# echo.net
KiCad netlist of a schematic drawn in Altium Designer
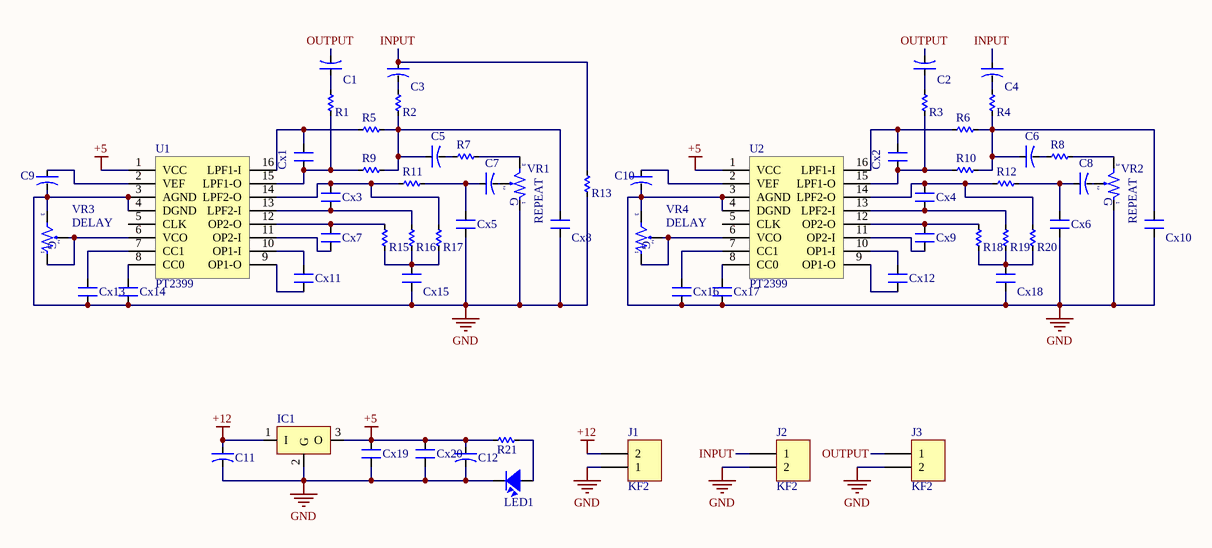
[diagram p0: echo.SchDoc]

(export (version "E")
  (design (tool "Eeschema 10.0.6"))
  (components
    (comp (ref "C1")
      (value "CN-ALU-DIP")
      (footprint "CA-ALU-5")
      (description "Capacitor (Semiconductor SIM Model)")
      (fields (field (name "PUBLISHER") "Altium Limited"))
      (libsource (lib "LIBRARY") (part "CN-ALU-DIP"))
    )
    (comp (ref "C2")
      (value "CN-ALU-DIP")
      (footprint "CA-ALU-5")
      (description "Capacitor (Semiconductor SIM Model)")
      (fields (field (name "PUBLISHER") "Altium Limited"))
      (libsource (lib "LIBRARY") (part "CN-ALU-DIP"))
    )
    (comp (ref "C3")
      (value "CN-ALU-DIP")
      (footprint "CA-ALU-5")
      (description "Capacitor (Semiconductor SIM Model)")
      (fields (field (name "PUBLISHER") "Altium Limited"))
      (libsource (lib "LIBRARY") (part "CN-ALU-DIP"))
    )
    (comp (ref "C4")
      (value "CN-ALU-DIP")
      (footprint "CA-ALU-5")
      (description "Capacitor (Semiconductor SIM Model)")
      (fields (field (name "PUBLISHER") "Altium Limited"))
      (libsource (lib "LIBRARY") (part "CN-ALU-DIP"))
    )
    (comp (ref "C5")
      (value "CN-ALU-DIP")
      (footprint "CA-ALU-5")
      (description "Capacitor (Semiconductor SIM Model)")
      (fields (field (name "PUBLISHER") "Altium Limited"))
      (libsource (lib "LIBRARY") (part "CN-ALU-DIP"))
    )
    (comp (ref "C6")
      (value "CN-ALU-DIP")
      (footprint "CA-ALU-5")
      (description "Capacitor (Semiconductor SIM Model)")
      (fields (field (name "PUBLISHER") "Altium Limited"))
      (libsource (lib "LIBRARY") (part "CN-ALU-DIP"))
    )
    (comp (ref "C7")
      (value "CN-ALU-DIP")
      (footprint "CA-ALU-5")
      (description "Capacitor (Semiconductor SIM Model)")
      (fields (field (name "PUBLISHER") "Altium Limited"))
      (libsource (lib "LIBRARY") (part "CN-ALU-DIP"))
    )
    (comp (ref "C8")
      (value "CN-ALU-DIP")
      (footprint "CA-ALU-5")
      (description "Capacitor (Semiconductor SIM Model)")
      (fields (field (name "PUBLISHER") "Altium Limited"))
      (libsource (lib "LIBRARY") (part "CN-ALU-DIP"))
    )
    (comp (ref "C9")
      (value "CN-ALU-DIP")
      (footprint "CA-ALU-5")
      (description "Capacitor (Semiconductor SIM Model)")
      (fields (field (name "PUBLISHER") "Altium Limited"))
      (libsource (lib "LIBRARY") (part "CN-ALU-DIP"))
    )
    (comp (ref "C10")
      (value "CN-ALU-DIP")
      (footprint "CA-ALU-5")
      (description "Capacitor (Semiconductor SIM Model)")
      (fields (field (name "PUBLISHER") "Altium Limited"))
      (libsource (lib "LIBRARY") (part "CN-ALU-DIP"))
    )
    (comp (ref "C11")
      (value "CN-ALU-DIP")
      (footprint "CA-ALU-6.3")
      (description "Capacitor (Semiconductor SIM Model)")
      (fields (field (name "PUBLISHER") "Altium Limited"))
      (libsource (lib "LIBRARY") (part "CN-ALU-DIP"))
    )
    (comp (ref "C12")
      (value "CN-ALU-DIP")
      (footprint "CA-ALU-8")
      (description "Capacitor (Semiconductor SIM Model)")
      (fields (field (name "PUBLISHER") "Altium Limited"))
      (libsource (lib "LIBRARY") (part "CN-ALU-DIP"))
    )
    (comp (ref "Cx1") (value "XXpF") (footprint "CN1.5") (libsource (lib "LIBRARY") (part "CN")))
    (comp (ref "Cx2") (value "XXpF") (footprint "CN1.5") (libsource (lib "LIBRARY") (part "CN")))
    (comp (ref "Cx3") (value "XXpF") (footprint "CN1.5") (libsource (lib "LIBRARY") (part "CN")))
    (comp (ref "Cx4") (value "XXpF") (footprint "CN1.5") (libsource (lib "LIBRARY") (part "CN")))
    (comp (ref "Cx5") (value "XXpF") (footprint "CN1.5") (libsource (lib "LIBRARY") (part "CN")))
    (comp (ref "Cx6") (value "XXpF") (footprint "CN1.5") (libsource (lib "LIBRARY") (part "CN")))
    (comp (ref "Cx7") (value "XXpF") (footprint "CN1.5") (libsource (lib "LIBRARY") (part "CN")))
    (comp (ref "Cx8") (value "XXpF") (footprint "CN1.5") (libsource (lib "LIBRARY") (part "CN")))
    (comp (ref "Cx9") (value "XXpF") (footprint "CN1.5") (libsource (lib "LIBRARY") (part "CN")))
    (comp (ref "Cx10") (value "XXpF") (footprint "CN1.5") (libsource (lib "LIBRARY") (part "CN")))
    (comp (ref "Cx11") (value "XXpF") (footprint "CN1.5") (libsource (lib "LIBRARY") (part "CN")))
    (comp (ref "Cx12") (value "XXpF") (footprint "CN1.5") (libsource (lib "LIBRARY") (part "CN")))
    (comp (ref "Cx13") (value "XXpF") (footprint "CN1.5") (libsource (lib "LIBRARY") (part "CN")))
    (comp (ref "Cx14") (value "XXpF") (footprint "CN1.5") (libsource (lib "LIBRARY") (part "CN")))
    (comp (ref "Cx15") (value "XXpF") (footprint "CN1.5") (libsource (lib "LIBRARY") (part "CN")))
    (comp (ref "Cx16") (value "XXpF") (footprint "CN1.5") (libsource (lib "LIBRARY") (part "CN")))
    (comp (ref "Cx17") (value "XXpF") (footprint "CN1.5") (libsource (lib "LIBRARY") (part "CN")))
    (comp (ref "Cx18") (value "XXpF") (footprint "CN1.5") (libsource (lib "LIBRARY") (part "CN")))
    (comp (ref "Cx19") (value "XXpF") (footprint "CN1.5") (libsource (lib "LIBRARY") (part "CN")))
    (comp (ref "Cx20") (value "XXpF") (footprint "CN1.5") (libsource (lib "LIBRARY") (part "CN")))
    (comp (ref "IC1")
      (value "LM78xx")
      (footprint "TO220-123")
      (description "Positive Voltage Regulator")
      (fields (field (name "PUBLISHER") "Altium Limited"))
      (libsource (lib "LIBRARY") (part "LM78xx"))
    )
    (comp (ref "J1")
      (value "KF2")
      (footprint "KF2-5.08")
      (fields
        (field (name "MANUFACTURER") "Würth Elektronik eiSos GmbH")
        (field (name "PARTNO") "691103110002")
        (field (name "CREATED BY") "Karrer Zheng")
      )
      (libsource (lib "") (part "KF2_1"))
    )
    (comp (ref "J2")
      (value "KF2")
      (footprint "KF2-5.08")
      (fields
        (field (name "MANUFACTURER") "Würth Elektronik eiSos GmbH")
        (field (name "PARTNO") "691103110002")
        (field (name "CREATED BY") "Karrer Zheng")
      )
      (libsource (lib "LIBRARY") (part "KF2"))
    )
    (comp (ref "J3")
      (value "KF2")
      (footprint "KF2-5.08")
      (fields
        (field (name "MANUFACTURER") "Würth Elektronik eiSos GmbH")
        (field (name "PARTNO") "691103110002")
        (field (name "CREATED BY") "Karrer Zheng")
      )
      (libsource (lib "LIBRARY") (part "KF2"))
    )
    (comp (ref "LED1")
      (value "LED")
      (footprint "LED-5-BLUE")
      (description "LED Single colour Green and Red")
      (libsource (lib "LIBRARY") (part "LED"))
    )
    (comp (ref "R1")
      (value "Res")
      (footprint "RES-1/4W-SMALL")
      (fields
        (field (name "MANUFACTURER") "Generic Components")
        (field (name "PUBLISHER") "Altium Hobart Technology Centre")
      )
      (libsource (lib "LIBRARY") (part "Res"))
    )
    (comp (ref "R2")
      (value "Res")
      (footprint "RES-1/4W-SMALL")
      (fields
        (field (name "MANUFACTURER") "Generic Components")
        (field (name "PUBLISHER") "Altium Hobart Technology Centre")
      )
      (libsource (lib "LIBRARY") (part "Res"))
    )
    (comp (ref "R3")
      (value "Res")
      (footprint "RES-1/4W-SMALL")
      (fields
        (field (name "MANUFACTURER") "Generic Components")
        (field (name "PUBLISHER") "Altium Hobart Technology Centre")
      )
      (libsource (lib "LIBRARY") (part "Res"))
    )
    (comp (ref "R4")
      (value "Res")
      (footprint "RES-1/4W-SMALL")
      (fields
        (field (name "MANUFACTURER") "Generic Components")
        (field (name "PUBLISHER") "Altium Hobart Technology Centre")
      )
      (libsource (lib "LIBRARY") (part "Res"))
    )
    (comp (ref "R5")
      (value "Res")
      (footprint "RES-1/4W-SMALL")
      (fields
        (field (name "MANUFACTURER") "Generic Components")
        (field (name "PUBLISHER") "Altium Hobart Technology Centre")
      )
      (libsource (lib "LIBRARY") (part "Res"))
    )
    (comp (ref "R6")
      (value "Res")
      (footprint "RES-1/4W-SMALL")
      (fields
        (field (name "MANUFACTURER") "Generic Components")
        (field (name "PUBLISHER") "Altium Hobart Technology Centre")
      )
      (libsource (lib "LIBRARY") (part "Res"))
    )
    (comp (ref "R7")
      (value "Res")
      (footprint "RES-1/4W-SMALL")
      (fields
        (field (name "MANUFACTURER") "Generic Components")
        (field (name "PUBLISHER") "Altium Hobart Technology Centre")
      )
      (libsource (lib "LIBRARY") (part "Res"))
    )
    (comp (ref "R8")
      (value "Res")
      (footprint "RES-1/4W-SMALL")
      (fields
        (field (name "MANUFACTURER") "Generic Components")
        (field (name "PUBLISHER") "Altium Hobart Technology Centre")
      )
      (libsource (lib "LIBRARY") (part "Res"))
    )
    (comp (ref "R9")
      (value "Res")
      (footprint "RES-1/4W-SMALL")
      (fields
        (field (name "MANUFACTURER") "Generic Components")
        (field (name "PUBLISHER") "Altium Hobart Technology Centre")
      )
      (libsource (lib "LIBRARY") (part "Res"))
    )
    (comp (ref "R10")
      (value "Res")
      (footprint "RES-1/4W-SMALL")
      (fields
        (field (name "MANUFACTURER") "Generic Components")
        (field (name "PUBLISHER") "Altium Hobart Technology Centre")
      )
      (libsource (lib "LIBRARY") (part "Res"))
    )
    (comp (ref "R11")
      (value "Res")
      (footprint "RES-1/4W-SMALL")
      (fields
        (field (name "MANUFACTURER") "Generic Components")
        (field (name "PUBLISHER") "Altium Hobart Technology Centre")
      )
      (libsource (lib "LIBRARY") (part "Res"))
    )
    (comp (ref "R12")
      (value "Res")
      (footprint "RES-1/4W-SMALL")
      (fields
        (field (name "MANUFACTURER") "Generic Components")
        (field (name "PUBLISHER") "Altium Hobart Technology Centre")
      )
      (libsource (lib "LIBRARY") (part "Res"))
    )
    (comp (ref "R13")
      (value "Res")
      (footprint "RES-1/4W-SMALL")
      (fields
        (field (name "MANUFACTURER") "Generic Components")
        (field (name "PUBLISHER") "Altium Hobart Technology Centre")
      )
      (libsource (lib "LIBRARY") (part "Res"))
    )
    (comp (ref "R15")
      (value "Res")
      (footprint "RES-1/4W-SMALL")
      (fields
        (field (name "MANUFACTURER") "Generic Components")
        (field (name "PUBLISHER") "Altium Hobart Technology Centre")
      )
      (libsource (lib "LIBRARY") (part "Res"))
    )
    (comp (ref "R16")
      (value "Res")
      (footprint "RES-1/4W-SMALL")
      (fields
        (field (name "MANUFACTURER") "Generic Components")
        (field (name "PUBLISHER") "Altium Hobart Technology Centre")
      )
      (libsource (lib "LIBRARY") (part "Res"))
    )
    (comp (ref "R17")
      (value "Res")
      (footprint "RES-1/4W-SMALL")
      (fields
        (field (name "MANUFACTURER") "Generic Components")
        (field (name "PUBLISHER") "Altium Hobart Technology Centre")
      )
      (libsource (lib "LIBRARY") (part "Res"))
    )
    (comp (ref "R18")
      (value "Res")
      (footprint "RES-1/4W-SMALL")
      (fields
        (field (name "MANUFACTURER") "Generic Components")
        (field (name "PUBLISHER") "Altium Hobart Technology Centre")
      )
      (libsource (lib "LIBRARY") (part "Res"))
    )
    (comp (ref "R19")
      (value "Res")
      (footprint "RES-1/4W-SMALL")
      (fields
        (field (name "MANUFACTURER") "Generic Components")
        (field (name "PUBLISHER") "Altium Hobart Technology Centre")
      )
      (libsource (lib "LIBRARY") (part "Res"))
    )
    (comp (ref "R20")
      (value "Res")
      (footprint "RES-1/4W-SMALL")
      (fields
        (field (name "MANUFACTURER") "Generic Components")
        (field (name "PUBLISHER") "Altium Hobart Technology Centre")
      )
      (libsource (lib "LIBRARY") (part "Res"))
    )
    (comp (ref "R21")
      (value "Res")
      (footprint "RES-1/4W-SMALL")
      (fields
        (field (name "MANUFACTURER") "Generic Components")
        (field (name "PUBLISHER") "Altium Hobart Technology Centre")
      )
      (libsource (lib "LIBRARY") (part "Res"))
    )
    (comp (ref "U1")
      (value "PT2399")
      (footprint "DIP16")
      (description "Reverb")
      (libsource (lib "LIBRARY") (part "PT2399"))
    )
    (comp (ref "U2")
      (value "PT2399")
      (footprint "DIP16")
      (description "Reverb")
      (libsource (lib "LIBRARY") (part "PT2399"))
    )
    (comp (ref "VR1")
      (value "REPEAT")
      (footprint "VR-S1")
      (description "Var Resistor")
      (libsource (lib "LIBRARY") (part "VR-S"))
    )
    (comp (ref "VR2")
      (value "REPEAT")
      (footprint "VR-S1")
      (description "Var Resistor")
      (libsource (lib "LIBRARY") (part "VR-S"))
    )
    (comp (ref "VR3")
      (value "DELAY")
      (footprint "VR-S1")
      (description "Var Resistor")
      (libsource (lib "LIBRARY") (part "VR-S"))
    )
    (comp (ref "VR4")
      (value "DELAY")
      (footprint "VR-S1")
      (description "Var Resistor")
      (libsource (lib "LIBRARY") (part "VR-S"))
    )
  )
  (nets
    (net (code "1") (name "+5") (class "Default")
      (node (ref "C12") (pin "1") (pinfunction "1_1") (pintype "passive"))
      (node (ref "Cx19") (pin "2") (pinfunction "2_2") (pintype "passive"))
      (node (ref "Cx20") (pin "2") (pinfunction "2_2") (pintype "passive"))
      (node (ref "IC1") (pin "3") (pinfunction "O_3") (pintype "power_in"))
      (node (ref "R21") (pin "1") (pinfunction "1_1") (pintype "passive"))
      (node (ref "U1") (pin "1") (pinfunction "VCC_1") (pintype "passive"))
      (node (ref "U2") (pin "1") (pinfunction "VCC_1") (pintype "passive"))
    )
    (net (code "2") (name "+12") (class "Default")
      (node (ref "C11") (pin "1") (pinfunction "1_1") (pintype "passive"))
      (node (ref "IC1") (pin "1") (pinfunction "I_1") (pintype "power_in"))
      (node (ref "J1") (pin "2") (pinfunction "2_2") (pintype "passive"))
    )
    (net (code "3") (name "/INPUT") (class "Default")
      (node (ref "C3") (pin "1") (pinfunction "1_1") (pintype "passive"))
      (node (ref "C4") (pin "1") (pinfunction "1_1") (pintype "passive"))
      (node (ref "J2") (pin "1") (pinfunction "1_1") (pintype "passive"))
      (node (ref "R13") (pin "2") (pinfunction "2_2") (pintype "passive"))
    )
    (net (code "4") (name "/OUTPUT") (class "Default")
      (node (ref "C1") (pin "2") (pinfunction "2_2") (pintype "passive"))
      (node (ref "C2") (pin "2") (pinfunction "2_2") (pintype "passive"))
      (node (ref "J3") (pin "1") (pinfunction "1_1") (pintype "passive"))
    )
    (net (code "5") (name "GND") (class "Default")
      (node (ref "C10") (pin "2") (pinfunction "2_2") (pintype "passive"))
      (node (ref "C11") (pin "2") (pinfunction "2_2") (pintype "passive"))
      (node (ref "C12") (pin "2") (pinfunction "2_2") (pintype "passive"))
      (node (ref "C9") (pin "2") (pinfunction "2_2") (pintype "passive"))
      (node (ref "Cx10") (pin "2") (pinfunction "2_2") (pintype "passive"))
      (node (ref "Cx13") (pin "2") (pinfunction "2_2") (pintype "passive"))
      (node (ref "Cx14") (pin "2") (pinfunction "2_2") (pintype "passive"))
      (node (ref "Cx15") (pin "2") (pinfunction "2_2") (pintype "passive"))
      (node (ref "Cx16") (pin "2") (pinfunction "2_2") (pintype "passive"))
      (node (ref "Cx17") (pin "2") (pinfunction "2_2") (pintype "passive"))
      (node (ref "Cx18") (pin "2") (pinfunction "2_2") (pintype "passive"))
      (node (ref "Cx19") (pin "1") (pinfunction "1_1") (pintype "passive"))
      (node (ref "Cx20") (pin "1") (pinfunction "1_1") (pintype "passive"))
      (node (ref "Cx5") (pin "2") (pinfunction "2_2") (pintype "passive"))
      (node (ref "Cx6") (pin "2") (pinfunction "2_2") (pintype "passive"))
      (node (ref "Cx8") (pin "2") (pinfunction "2_2") (pintype "passive"))
      (node (ref "IC1") (pin "2") (pinfunction "G_2") (pintype "power_in"))
      (node (ref "J1") (pin "1") (pinfunction "1_1") (pintype "passive"))
      (node (ref "J2") (pin "2") (pinfunction "2_2") (pintype "passive"))
      (node (ref "J3") (pin "2") (pinfunction "2_2") (pintype "passive"))
      (node (ref "LED1") (pin "2") (pinfunction "2_2") (pintype "passive"))
      (node (ref "R13") (pin "1") (pinfunction "1_1") (pintype "passive"))
      (node (ref "U1") (pin "3") (pinfunction "AGND_3") (pintype "passive"))
      (node (ref "U1") (pin "4") (pinfunction "DGND_4") (pintype "passive"))
      (node (ref "U2") (pin "3") (pinfunction "AGND_3") (pintype "passive"))
      (node (ref "U2") (pin "4") (pinfunction "DGND_4") (pintype "passive"))
      (node (ref "VR1") (pin "1") (pinfunction "1_1") (pintype "passive"))
      (node (ref "VR2") (pin "1") (pinfunction "1_1") (pintype "passive"))
      (node (ref "VR3") (pin "3") (pinfunction "3_3") (pintype "passive"))
      (node (ref "VR4") (pin "3") (pinfunction "3_3") (pintype "passive"))
    )
    (net (code "6") (name "Net-(C1-Pad1)") (class "Default")
      (node (ref "C1") (pin "1") (pinfunction "1_1") (pintype "passive"))
      (node (ref "R1") (pin "1") (pinfunction "1_1") (pintype "passive"))
    )
    (net (code "7") (name "Net-(C2-Pad1)") (class "Default")
      (node (ref "C2") (pin "1") (pinfunction "1_1") (pintype "passive"))
      (node (ref "R3") (pin "1") (pinfunction "1_1") (pintype "passive"))
    )
    (net (code "8") (name "Net-(C3-Pad2)") (class "Default")
      (node (ref "C3") (pin "2") (pinfunction "2_2") (pintype "passive"))
      (node (ref "R2") (pin "2") (pinfunction "2_2") (pintype "passive"))
    )
    (net (code "9") (name "Net-(C4-Pad2)") (class "Default")
      (node (ref "C4") (pin "2") (pinfunction "2_2") (pintype "passive"))
      (node (ref "R4") (pin "2") (pinfunction "2_2") (pintype "passive"))
    )
    (net (code "10") (name "Net-(C5-Pad1)") (class "Default")
      (node (ref "C5") (pin "1") (pinfunction "1_1") (pintype "passive"))
      (node (ref "Cx8") (pin "1") (pinfunction "1_1") (pintype "passive"))
      (node (ref "R2") (pin "1") (pinfunction "1_1") (pintype "passive"))
      (node (ref "R5") (pin "1") (pinfunction "1_1") (pintype "passive"))
      (node (ref "R9") (pin "1") (pinfunction "1_1") (pintype "passive"))
    )
    (net (code "11") (name "Net-(C5-Pad2)") (class "Default")
      (node (ref "C5") (pin "2") (pinfunction "2_2") (pintype "passive"))
      (node (ref "R7") (pin "2") (pinfunction "2_2") (pintype "passive"))
    )
    (net (code "12") (name "Net-(C6-Pad1)") (class "Default")
      (node (ref "C6") (pin "1") (pinfunction "1_1") (pintype "passive"))
      (node (ref "Cx10") (pin "1") (pinfunction "1_1") (pintype "passive"))
      (node (ref "R10") (pin "1") (pinfunction "1_1") (pintype "passive"))
      (node (ref "R4") (pin "1") (pinfunction "1_1") (pintype "passive"))
      (node (ref "R6") (pin "1") (pinfunction "1_1") (pintype "passive"))
    )
    (net (code "13") (name "Net-(C6-Pad2)") (class "Default")
      (node (ref "C6") (pin "2") (pinfunction "2_2") (pintype "passive"))
      (node (ref "R8") (pin "2") (pinfunction "2_2") (pintype "passive"))
    )
    (net (code "14") (name "Net-(C7-Pad1)") (class "Default")
      (node (ref "C7") (pin "1") (pinfunction "1_1") (pintype "passive"))
      (node (ref "Cx5") (pin "1") (pinfunction "1_1") (pintype "passive"))
      (node (ref "R11") (pin "1") (pinfunction "1_1") (pintype "passive"))
    )
    (net (code "15") (name "Net-(C7-Pad2)") (class "Default")
      (node (ref "C7") (pin "2") (pinfunction "2_2") (pintype "passive"))
      (node (ref "VR1") (pin "2") (pinfunction "2_2") (pintype "passive"))
    )
    (net (code "16") (name "Net-(C8-Pad1)") (class "Default")
      (node (ref "C8") (pin "1") (pinfunction "1_1") (pintype "passive"))
      (node (ref "Cx6") (pin "1") (pinfunction "1_1") (pintype "passive"))
      (node (ref "R12") (pin "1") (pinfunction "1_1") (pintype "passive"))
    )
    (net (code "17") (name "Net-(C8-Pad2)") (class "Default")
      (node (ref "C8") (pin "2") (pinfunction "2_2") (pintype "passive"))
      (node (ref "VR2") (pin "2") (pinfunction "2_2") (pintype "passive"))
    )
    (net (code "18") (name "Net-(Cx15-Pad1)") (class "Default")
      (node (ref "Cx15") (pin "1") (pinfunction "1_1") (pintype "passive"))
      (node (ref "R15") (pin "2") (pinfunction "2_2") (pintype "passive"))
      (node (ref "R16") (pin "2") (pinfunction "2_2") (pintype "passive"))
      (node (ref "R17") (pin "2") (pinfunction "2_2") (pintype "passive"))
    )
    (net (code "19") (name "Net-(Cx18-Pad1)") (class "Default")
      (node (ref "Cx18") (pin "1") (pinfunction "1_1") (pintype "passive"))
      (node (ref "R18") (pin "2") (pinfunction "2_2") (pintype "passive"))
      (node (ref "R19") (pin "2") (pinfunction "2_2") (pintype "passive"))
      (node (ref "R20") (pin "2") (pinfunction "2_2") (pintype "passive"))
    )
    (net (code "20") (name "Net-(LED1-Pad1)") (class "Default")
      (node (ref "LED1") (pin "1") (pinfunction "1_1") (pintype "passive"))
      (node (ref "R21") (pin "2") (pinfunction "2_2") (pintype "passive"))
    )
    (net (code "21") (name "Net-(R7-Pad1)") (class "Default")
      (node (ref "R7") (pin "1") (pinfunction "1_1") (pintype "passive"))
      (node (ref "VR1") (pin "3") (pinfunction "3_3") (pintype "passive"))
    )
    (net (code "22") (name "Net-(R8-Pad1)") (class "Default")
      (node (ref "R8") (pin "1") (pinfunction "1_1") (pintype "passive"))
      (node (ref "VR2") (pin "3") (pinfunction "3_3") (pintype "passive"))
    )
    (net (code "23") (name "Net-(U1-CC0)") (class "Default")
      (node (ref "Cx14") (pin "1") (pinfunction "1_1") (pintype "passive"))
      (node (ref "U1") (pin "8") (pinfunction "CC0_8") (pintype "passive"))
    )
    (net (code "24") (name "Net-(U1-CC1)") (class "Default")
      (node (ref "Cx13") (pin "1") (pinfunction "1_1") (pintype "passive"))
      (node (ref "U1") (pin "7") (pinfunction "CC1_7") (pintype "passive"))
    )
    (net (code "25") (name "Net-(U1-LPF1-I)") (class "Default")
      (node (ref "Cx1") (pin "1") (pinfunction "1_1") (pintype "passive"))
      (node (ref "R5") (pin "2") (pinfunction "2_2") (pintype "passive"))
      (node (ref "U1") (pin "16") (pinfunction "LPF1-I_16") (pintype "passive"))
    )
    (net (code "26") (name "Net-(U1-LPF1-O)") (class "Default")
      (node (ref "Cx1") (pin "2") (pinfunction "2_2") (pintype "passive"))
      (node (ref "R1") (pin "2") (pinfunction "2_2") (pintype "passive"))
      (node (ref "R9") (pin "2") (pinfunction "2_2") (pintype "passive"))
      (node (ref "U1") (pin "15") (pinfunction "LPF1-O_15") (pintype "passive"))
    )
    (net (code "27") (name "Net-(U1-LPF2-I)") (class "Default")
      (node (ref "Cx3") (pin "2") (pinfunction "2_2") (pintype "passive"))
      (node (ref "R16") (pin "1") (pinfunction "1_1") (pintype "passive"))
      (node (ref "U1") (pin "13") (pinfunction "LPF2-I_13") (pintype "passive"))
    )
    (net (code "28") (name "Net-(U1-LPF2-O)") (class "Default")
      (node (ref "Cx3") (pin "1") (pinfunction "1_1") (pintype "passive"))
      (node (ref "R11") (pin "2") (pinfunction "2_2") (pintype "passive"))
      (node (ref "R17") (pin "1") (pinfunction "1_1") (pintype "passive"))
      (node (ref "U1") (pin "14") (pinfunction "LPF2-O_14") (pintype "passive"))
    )
    (net (code "29") (name "Net-(U1-OP1-I)") (class "Default")
      (node (ref "Cx11") (pin "1") (pinfunction "1_1") (pintype "passive"))
      (node (ref "U1") (pin "10") (pinfunction "OP1-I_10") (pintype "passive"))
    )
    (net (code "30") (name "Net-(U1-OP1-O)") (class "Default")
      (node (ref "Cx11") (pin "2") (pinfunction "2_2") (pintype "passive"))
      (node (ref "U1") (pin "9") (pinfunction "OP1-O_9") (pintype "passive"))
    )
    (net (code "31") (name "Net-(U1-OP2-I)") (class "Default")
      (node (ref "Cx7") (pin "2") (pinfunction "2_2") (pintype "passive"))
      (node (ref "U1") (pin "11") (pinfunction "OP2-I_11") (pintype "passive"))
    )
    (net (code "32") (name "Net-(U1-OP2-O)") (class "Default")
      (node (ref "Cx7") (pin "1") (pinfunction "1_1") (pintype "passive"))
      (node (ref "R15") (pin "1") (pinfunction "1_1") (pintype "passive"))
      (node (ref "U1") (pin "12") (pinfunction "OP2-O_12") (pintype "passive"))
    )
    (net (code "33") (name "Net-(U1-VCO)") (class "Default")
      (node (ref "U1") (pin "6") (pinfunction "VCO_6") (pintype "passive"))
      (node (ref "VR3") (pin "1") (pinfunction "1_1") (pintype "passive"))
      (node (ref "VR3") (pin "2") (pinfunction "2_2") (pintype "passive"))
    )
    (net (code "34") (name "Net-(U1-VEF)") (class "Default")
      (node (ref "C9") (pin "1") (pinfunction "1_1") (pintype "passive"))
      (node (ref "U1") (pin "2") (pinfunction "VEF_2") (pintype "passive"))
    )
    (net (code "35") (name "Net-(U2-CC0)") (class "Default")
      (node (ref "Cx17") (pin "1") (pinfunction "1_1") (pintype "passive"))
      (node (ref "U2") (pin "8") (pinfunction "CC0_8") (pintype "passive"))
    )
    (net (code "36") (name "Net-(U2-CC1)") (class "Default")
      (node (ref "Cx16") (pin "1") (pinfunction "1_1") (pintype "passive"))
      (node (ref "U2") (pin "7") (pinfunction "CC1_7") (pintype "passive"))
    )
    (net (code "37") (name "Net-(U2-LPF1-I)") (class "Default")
      (node (ref "Cx2") (pin "1") (pinfunction "1_1") (pintype "passive"))
      (node (ref "R6") (pin "2") (pinfunction "2_2") (pintype "passive"))
      (node (ref "U2") (pin "16") (pinfunction "LPF1-I_16") (pintype "passive"))
    )
    (net (code "38") (name "Net-(U2-LPF1-O)") (class "Default")
      (node (ref "Cx2") (pin "2") (pinfunction "2_2") (pintype "passive"))
      (node (ref "R10") (pin "2") (pinfunction "2_2") (pintype "passive"))
      (node (ref "R3") (pin "2") (pinfunction "2_2") (pintype "passive"))
      (node (ref "U2") (pin "15") (pinfunction "LPF1-O_15") (pintype "passive"))
    )
    (net (code "39") (name "Net-(U2-LPF2-I)") (class "Default")
      (node (ref "Cx4") (pin "2") (pinfunction "2_2") (pintype "passive"))
      (node (ref "R19") (pin "1") (pinfunction "1_1") (pintype "passive"))
      (node (ref "U2") (pin "13") (pinfunction "LPF2-I_13") (pintype "passive"))
    )
    (net (code "40") (name "Net-(U2-LPF2-O)") (class "Default")
      (node (ref "Cx4") (pin "1") (pinfunction "1_1") (pintype "passive"))
      (node (ref "R12") (pin "2") (pinfunction "2_2") (pintype "passive"))
      (node (ref "R20") (pin "1") (pinfunction "1_1") (pintype "passive"))
      (node (ref "U2") (pin "14") (pinfunction "LPF2-O_14") (pintype "passive"))
    )
    (net (code "41") (name "Net-(U2-OP1-I)") (class "Default")
      (node (ref "Cx12") (pin "1") (pinfunction "1_1") (pintype "passive"))
      (node (ref "U2") (pin "10") (pinfunction "OP1-I_10") (pintype "passive"))
    )
    (net (code "42") (name "Net-(U2-OP1-O)") (class "Default")
      (node (ref "Cx12") (pin "2") (pinfunction "2_2") (pintype "passive"))
      (node (ref "U2") (pin "9") (pinfunction "OP1-O_9") (pintype "passive"))
    )
    (net (code "43") (name "Net-(U2-OP2-I)") (class "Default")
      (node (ref "Cx9") (pin "2") (pinfunction "2_2") (pintype "passive"))
      (node (ref "U2") (pin "11") (pinfunction "OP2-I_11") (pintype "passive"))
    )
    (net (code "44") (name "Net-(U2-OP2-O)") (class "Default")
      (node (ref "Cx9") (pin "1") (pinfunction "1_1") (pintype "passive"))
      (node (ref "R18") (pin "1") (pinfunction "1_1") (pintype "passive"))
      (node (ref "U2") (pin "12") (pinfunction "OP2-O_12") (pintype "passive"))
    )
    (net (code "45") (name "Net-(U2-VCO)") (class "Default")
      (node (ref "U2") (pin "6") (pinfunction "VCO_6") (pintype "passive"))
      (node (ref "VR4") (pin "1") (pinfunction "1_1") (pintype "passive"))
      (node (ref "VR4") (pin "2") (pinfunction "2_2") (pintype "passive"))
    )
    (net (code "46") (name "Net-(U2-VEF)") (class "Default")
      (node (ref "C10") (pin "1") (pinfunction "1_1") (pintype "passive"))
      (node (ref "U2") (pin "2") (pinfunction "VEF_2") (pintype "passive"))
    )
    (net (code "47") (name "unconnected-(U1-CLK-Pad5)") (class "Default")
      (node (ref "U1") (pin "5") (pinfunction "CLK_5") (pintype "passive"))
    )
    (net (code "48") (name "unconnected-(U2-CLK-Pad5)") (class "Default")
      (node (ref "U2") (pin "5") (pinfunction "CLK_5") (pintype "passive"))
    )
  )
)
